# untitled.net
KiCad netlist of a schematic drawn in EAGLE
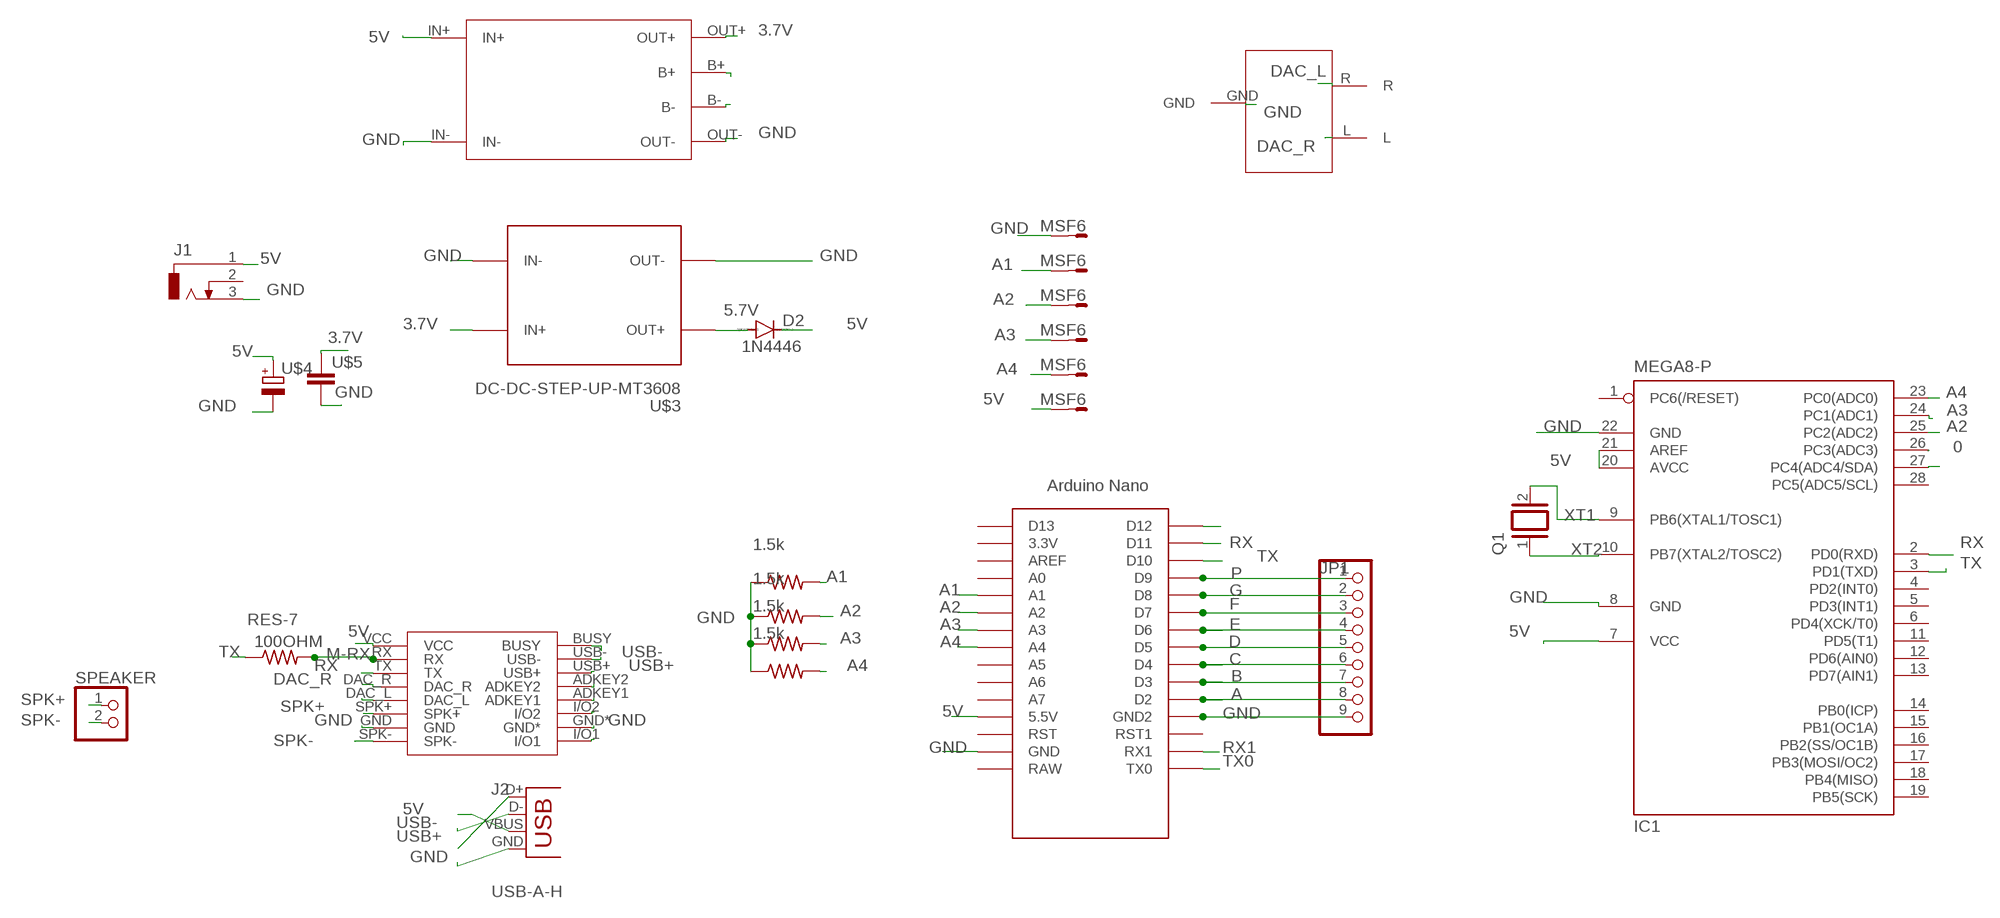
[diagram p0: schematic, sheet 1]

(export (version "E")
  (design (tool "Eeschema 10.0.6"))
  (components
    (comp (ref "1.5K")
      (value "1.5k")
      (footprint "eagle-import:0204_7")
      (libsource (lib "eagle-import") (part "RES-7"))
    )
    (comp (ref "100OHM")
      (value "RES-7")
      (footprint "eagle-import:0204_7")
      (libsource (lib "eagle-import") (part "RES-7"))
    )
    (comp (ref "100OHM2")
      (value "1.5k")
      (footprint "eagle-import:0204_7")
      (libsource (lib "eagle-import") (part "RES-7"))
    )
    (comp (ref "100OHM3")
      (value "1.5k")
      (footprint "eagle-import:0204_7")
      (libsource (lib "eagle-import") (part "RES-7"))
    )
    (comp (ref "100OHM4")
      (value "1.5k")
      (footprint "eagle-import:0204_7")
      (libsource (lib "eagle-import") (part "RES-7"))
    )
    (comp (ref "D2")
      (value "1N4446")
      (footprint "eagle-import:DO35-10")
      (libsource (lib "eagle-import") (part "1N4446"))
    )
    (comp (ref "IC1")
      (value "MEGA8-P")
      (footprint "eagle-import:DIL28-3")
      (libsource (lib "eagle-import") (part "MEGA8-P"))
    )
    (comp (ref "J1")
      (value "CON_JACK")
      (footprint "eagle-import:DCJ0303")
      (libsource (lib "eagle-import") (part "CON_JACK"))
    )
    (comp (ref "J2")
      (value "USB-A-H")
      (footprint "eagle-import:USB-A-H")
      (libsource (lib "eagle-import") (part "USB-A-H"))
    )
    (comp (ref "JP1")
      (value "PINHD-1X9")
      (footprint "eagle-import:1X09")
      (libsource (lib "eagle-import") (part "PINHD-1X9"))
    )
    (comp (ref "Q1")
      (value "XTAL/S")
      (footprint "eagle-import:QS")
      (libsource (lib "eagle-import") (part "XTAL/S"))
    )
    (comp (ref "SPEAKER")
      (value "PINHD-1X2")
      (footprint "eagle-import:1X02")
      (libsource (lib "eagle-import") (part "PINHD-1X2"))
    )
    (comp (ref "ST1")
      (value "MSF6")
      (footprint "eagle-import:MSF6")
      (libsource (lib "eagle-import") (part "MSF6"))
    )
    (comp (ref "U$1")
      (value "ARDUINO_NANO")
      (footprint "eagle-import:NANO")
      (libsource (lib "eagle-import") (part "ARDUINO_NANO"))
    )
    (comp (ref "U$2")
      (value "MP3_MODULE")
      (footprint "eagle-import:MP3_MODULE")
      (libsource (lib "eagle-import") (part "MP3_MODULE"))
    )
    (comp (ref "U$3")
      (value "DC-DC-STEP-UP-MT3608")
      (footprint "eagle-import:DC-DC-STEP-UP-MT3608")
      (libsource (lib "eagle-import") (part "DC-DC-STEP-UP-MT3608"))
    )
    (comp (ref "U$4")
      (value "CAP_POL")
      (footprint "eagle-import:E3,5-8")
      (libsource (lib "eagle-import") (part "CAP_POL"))
    )
    (comp (ref "U$5")
      (value "CAPACITOR")
      (footprint "eagle-import:C025-025X050")
      (libsource (lib "eagle-import") (part "CAPACITOR"))
    )
    (comp (ref "U$6")
      (value "LITHIUM_CHARGER_2A")
      (footprint "eagle-import:LITHIUM-CHARGER-1A")
      (libsource (lib "eagle-import") (part "LITHIUM_CHARGER_2A"))
    )
    (comp (ref "U$7")
      (value "EAR-PHONE-SOCKET")
      (footprint "eagle-import:EAR-PHONE-SOCKET")
      (libsource (lib "eagle-import") (part "EAR-PHONE-SOCKET"))
    )
  )
  (nets
    (net (code "1") (name "/0") (class "Default")
      (node (ref "IC1") (pin "26") (pinfunction "PC3(ADC3)_26") (pintype "bidirectional"))
    )
    (net (code "2") (name "/3.7V") (class "Default")
      (node (ref "U$3") (pin "IN+") (pinfunction "IN+_IN+") (pintype "bidirectional"))
      (node (ref "U$5") (pin "1") (pinfunction "1_1") (pintype "passive"))
      (node (ref "U$6") (pin "OUT+") (pinfunction "OUT+_OUT+") (pintype "bidirectional"))
    )
    (net (code "3") (name "/5.7V") (class "Default")
      (node (ref "D2") (pin "A") (pinfunction "A_A") (pintype "passive"))
      (node (ref "U$3") (pin "OUT+") (pinfunction "OUT+_OUT+") (pintype "bidirectional"))
    )
    (net (code "4") (name "/5V") (class "Default")
      (node (ref "D2") (pin "C") (pinfunction "C_C") (pintype "passive"))
      (node (ref "IC1") (pin "20") (pinfunction "AVCC_20") (pintype "power_in"))
      (node (ref "IC1") (pin "21") (pinfunction "AREF_21") (pintype "passive"))
      (node (ref "IC1") (pin "7") (pinfunction "VCC_7") (pintype "power_in"))
      (node (ref "J1") (pin "1") (pinfunction "1_1") (pintype "passive"))
      (node (ref "J2") (pin "VBUS") (pinfunction "VBUS_VBUS") (pintype "bidirectional"))
      (node (ref "ST1") (pin "1") (pinfunction "S_1") (pintype "passive"))
      (node (ref "U$1") (pin "5V") (pinfunction "5.5V_5V") (pintype "bidirectional"))
      (node (ref "U$2") (pin "VCC") (pinfunction "VCC_VCC") (pintype "bidirectional"))
      (node (ref "U$4") (pin "+") (pinfunction "+_+") (pintype "passive"))
      (node (ref "U$6") (pin "IN+") (pinfunction "IN+_IN+") (pintype "bidirectional"))
    )
    (net (code "5") (name "/A") (class "Default")
      (node (ref "JP1") (pin "8") (pinfunction "8_8") (pintype "passive"))
      (node (ref "U$1") (pin "D2") (pinfunction "D2_D2") (pintype "bidirectional"))
    )
    (net (code "6") (name "/A1") (class "Default")
      (node (ref "1.5K") (pin "2") (pinfunction "2_2") (pintype "passive"))
      (node (ref "ST1") (pin "5") (pinfunction "S_5") (pintype "passive"))
      (node (ref "U$1") (pin "A1") (pinfunction "A1_A1") (pintype "bidirectional"))
    )
    (net (code "7") (name "/A2") (class "Default")
      (node (ref "100OHM2") (pin "2") (pinfunction "2_2") (pintype "passive"))
      (node (ref "IC1") (pin "25") (pinfunction "PC2(ADC2)_25") (pintype "bidirectional"))
      (node (ref "ST1") (pin "4") (pinfunction "S_4") (pintype "passive"))
      (node (ref "U$1") (pin "A2") (pinfunction "A2_A2") (pintype "bidirectional"))
    )
    (net (code "8") (name "/A3") (class "Default")
      (node (ref "100OHM3") (pin "2") (pinfunction "2_2") (pintype "passive"))
      (node (ref "IC1") (pin "24") (pinfunction "PC1(ADC1)_24") (pintype "bidirectional"))
      (node (ref "ST1") (pin "3") (pinfunction "S_3") (pintype "passive"))
      (node (ref "U$1") (pin "A3") (pinfunction "A3_A3") (pintype "bidirectional"))
    )
    (net (code "9") (name "/A4") (class "Default")
      (node (ref "100OHM4") (pin "2") (pinfunction "2_2") (pintype "passive"))
      (node (ref "IC1") (pin "23") (pinfunction "PC0(ADC0)_23") (pintype "bidirectional"))
      (node (ref "ST1") (pin "2") (pinfunction "S_2") (pintype "passive"))
      (node (ref "U$1") (pin "A4") (pinfunction "A4_A4") (pintype "bidirectional"))
    )
    (net (code "10") (name "/B") (class "Default")
      (node (ref "JP1") (pin "7") (pinfunction "7_7") (pintype "passive"))
      (node (ref "U$1") (pin "D3") (pinfunction "D3_D3") (pintype "bidirectional"))
    )
    (net (code "11") (name "/C") (class "Default")
      (node (ref "JP1") (pin "6") (pinfunction "6_6") (pintype "passive"))
      (node (ref "U$1") (pin "D4") (pinfunction "D4_D4") (pintype "bidirectional"))
    )
    (net (code "12") (name "/D") (class "Default")
      (node (ref "JP1") (pin "5") (pinfunction "5_5") (pintype "passive"))
      (node (ref "U$1") (pin "D5") (pinfunction "D5_D5") (pintype "bidirectional"))
    )
    (net (code "13") (name "/DAC_L") (class "Default")
      (node (ref "U$2") (pin "DAC_L") (pinfunction "DAC_L_DAC_L") (pintype "bidirectional"))
      (node (ref "U$7") (pin "R") (pinfunction "R_R") (pintype "bidirectional"))
    )
    (net (code "14") (name "/DAC_R") (class "Default")
      (node (ref "U$2") (pin "DAC_R") (pinfunction "DAC_R_DAC_R") (pintype "bidirectional"))
      (node (ref "U$7") (pin "L") (pinfunction "L_L") (pintype "bidirectional"))
    )
    (net (code "15") (name "/E") (class "Default")
      (node (ref "JP1") (pin "4") (pinfunction "4_4") (pintype "passive"))
      (node (ref "U$1") (pin "D6") (pinfunction "D6_D6") (pintype "bidirectional"))
    )
    (net (code "16") (name "/F") (class "Default")
      (node (ref "JP1") (pin "3") (pinfunction "3_3") (pintype "passive"))
      (node (ref "U$1") (pin "D7") (pinfunction "D7_D7") (pintype "bidirectional"))
    )
    (net (code "17") (name "/G") (class "Default")
      (node (ref "JP1") (pin "2") (pinfunction "2_2") (pintype "passive"))
      (node (ref "U$1") (pin "D8") (pinfunction "D8_D8") (pintype "bidirectional"))
    )
    (net (code "18") (name "/GND") (class "Default")
      (node (ref "1.5K") (pin "1") (pinfunction "1_1") (pintype "passive"))
      (node (ref "100OHM2") (pin "1") (pinfunction "1_1") (pintype "passive"))
      (node (ref "100OHM3") (pin "1") (pinfunction "1_1") (pintype "passive"))
      (node (ref "100OHM4") (pin "1") (pinfunction "1_1") (pintype "passive"))
      (node (ref "IC1") (pin "22") (pinfunction "GND_22") (pintype "power_in"))
      (node (ref "IC1") (pin "8") (pinfunction "GND_8") (pintype "power_in"))
      (node (ref "J1") (pin "3") (pinfunction "3_3") (pintype "passive"))
      (node (ref "J2") (pin "GND") (pinfunction "GND_GND") (pintype "bidirectional"))
      (node (ref "JP1") (pin "9") (pinfunction "9_9") (pintype "passive"))
      (node (ref "ST1") (pin "6") (pinfunction "S_6") (pintype "passive"))
      (node (ref "U$1") (pin "GND") (pinfunction "GND_GND") (pintype "bidirectional"))
      (node (ref "U$1") (pin "GND1") (pinfunction "GND2_GND1") (pintype "bidirectional"))
      (node (ref "U$2") (pin "GND") (pinfunction "GND_GND") (pintype "bidirectional"))
      (node (ref "U$2") (pin "GND*") (pinfunction "GND*_GND*") (pintype "bidirectional"))
      (node (ref "U$3") (pin "IN-") (pinfunction "IN-_IN-") (pintype "bidirectional"))
      (node (ref "U$3") (pin "OUT-") (pinfunction "OUT-_OUT-") (pintype "bidirectional"))
      (node (ref "U$4") (pin "-") (pinfunction "-_-") (pintype "passive"))
      (node (ref "U$5") (pin "2") (pinfunction "2_2") (pintype "passive"))
      (node (ref "U$6") (pin "IN-") (pinfunction "IN-_IN-") (pintype "bidirectional"))
      (node (ref "U$6") (pin "OUT-") (pinfunction "OUT-_OUT-") (pintype "bidirectional"))
      (node (ref "U$7") (pin "GND") (pinfunction "GND_GND") (pintype "bidirectional"))
    )
    (net (code "19") (name "/M-RX") (class "Default")
      (node (ref "100OHM") (pin "2") (pinfunction "2_2") (pintype "passive"))
      (node (ref "U$2") (pin "RX") (pinfunction "RX_RX") (pintype "bidirectional"))
    )
    (net (code "20") (name "/P") (class "Default")
      (node (ref "JP1") (pin "1") (pinfunction "1_1") (pintype "passive"))
      (node (ref "U$1") (pin "D9") (pinfunction "D9_D9") (pintype "bidirectional"))
    )
    (net (code "21") (name "/RX") (class "Default")
      (node (ref "IC1") (pin "2") (pinfunction "PD0(RXD)_2") (pintype "bidirectional"))
      (node (ref "U$1") (pin "D11") (pinfunction "D11_D11") (pintype "bidirectional"))
      (node (ref "U$2") (pin "TX") (pinfunction "TX_TX") (pintype "bidirectional"))
    )
    (net (code "22") (name "/RX1") (class "Default")
      (node (ref "U$1") (pin "RX1") (pinfunction "RX1_RX1") (pintype "bidirectional"))
    )
    (net (code "23") (name "/SPK+") (class "Default")
      (node (ref "SPEAKER") (pin "1") (pinfunction "1_1") (pintype "passive"))
      (node (ref "U$2") (pin "SPK+") (pinfunction "SPK+_SPK+") (pintype "bidirectional"))
    )
    (net (code "24") (name "/SPK-") (class "Default")
      (node (ref "SPEAKER") (pin "2") (pinfunction "2_2") (pintype "passive"))
      (node (ref "U$2") (pin "SPK-") (pinfunction "SPK-_SPK-") (pintype "bidirectional"))
    )
    (net (code "25") (name "/TX") (class "Default")
      (node (ref "100OHM") (pin "1") (pinfunction "1_1") (pintype "passive"))
      (node (ref "IC1") (pin "3") (pinfunction "PD1(TXD)_3") (pintype "bidirectional"))
      (node (ref "U$1") (pin "D10") (pinfunction "D10_D10") (pintype "bidirectional"))
    )
    (net (code "26") (name "/TX0") (class "Default")
      (node (ref "U$1") (pin "TX0") (pinfunction "TX0_TX0") (pintype "bidirectional"))
    )
    (net (code "27") (name "/USB+") (class "Default")
      (node (ref "J2") (pin "D+") (pinfunction "D+_D+") (pintype "bidirectional"))
      (node (ref "U$2") (pin "USB+") (pinfunction "USB+_USB+") (pintype "bidirectional"))
    )
    (net (code "28") (name "/USB-") (class "Default")
      (node (ref "J2") (pin "D-") (pinfunction "D-_D-") (pintype "bidirectional"))
      (node (ref "U$2") (pin "USB-") (pinfunction "USB-_USB-") (pintype "bidirectional"))
    )
    (net (code "29") (name "/XT1") (class "Default")
      (node (ref "IC1") (pin "9") (pinfunction "PB6(XTAL1/TOSC1)_9") (pintype "bidirectional"))
      (node (ref "Q1") (pin "2") (pinfunction "2_2") (pintype "passive"))
    )
    (net (code "30") (name "/XT2") (class "Default")
      (node (ref "IC1") (pin "10") (pinfunction "PB7(XTAL2/TOSC2)_10") (pintype "bidirectional"))
      (node (ref "Q1") (pin "1") (pinfunction "1_1") (pintype "passive"))
    )
    (net (code "31") (name "unconnected-(IC1-PB0(ICP)-Pad14)") (class "Default")
      (node (ref "IC1") (pin "14") (pinfunction "PB0(ICP)_14") (pintype "bidirectional"))
    )
    (net (code "32") (name "unconnected-(IC1-PB1(OC1A)-Pad15)") (class "Default")
      (node (ref "IC1") (pin "15") (pinfunction "PB1(OC1A)_15") (pintype "bidirectional"))
    )
    (net (code "33") (name "unconnected-(IC1-PB2(SS{slash}OC1B)-Pad16)") (class "Default")
      (node (ref "IC1") (pin "16") (pinfunction "PB2(SS/OC1B)_16") (pintype "bidirectional"))
    )
    (net (code "34") (name "unconnected-(IC1-PB3(MOSI{slash}OC2)-Pad17)") (class "Default")
      (node (ref "IC1") (pin "17") (pinfunction "PB3(MOSI/OC2)_17") (pintype "bidirectional"))
    )
    (net (code "35") (name "unconnected-(IC1-PB4(MISO)-Pad18)") (class "Default")
      (node (ref "IC1") (pin "18") (pinfunction "PB4(MISO)_18") (pintype "bidirectional"))
    )
    (net (code "36") (name "unconnected-(IC1-PB5(SCK)-Pad19)") (class "Default")
      (node (ref "IC1") (pin "19") (pinfunction "PB5(SCK)_19") (pintype "bidirectional"))
    )
    (net (code "37") (name "unconnected-(IC1-PC4(ADC4{slash}SDA)-Pad27)") (class "Default")
      (node (ref "IC1") (pin "27") (pinfunction "PC4(ADC4/SDA)_27") (pintype "bidirectional"))
    )
    (net (code "38") (name "unconnected-(IC1-PC5(ADC5{slash}SCL)-Pad28)") (class "Default")
      (node (ref "IC1") (pin "28") (pinfunction "PC5(ADC5/SCL)_28") (pintype "bidirectional"))
    )
    (net (code "39") (name "unconnected-(IC1-PC6({slash}RESET)-Pad1)") (class "Default")
      (node (ref "IC1") (pin "1") (pinfunction "PC6(/RESET)_1") (pintype "bidirectional"))
    )
    (net (code "40") (name "unconnected-(IC1-PD2(INT0)-Pad4)") (class "Default")
      (node (ref "IC1") (pin "4") (pinfunction "PD2(INT0)_4") (pintype "bidirectional"))
    )
    (net (code "41") (name "unconnected-(IC1-PD3(INT1)-Pad5)") (class "Default")
      (node (ref "IC1") (pin "5") (pinfunction "PD3(INT1)_5") (pintype "bidirectional"))
    )
    (net (code "42") (name "unconnected-(IC1-PD4(XCK{slash}T0)-Pad6)") (class "Default")
      (node (ref "IC1") (pin "6") (pinfunction "PD4(XCK/T0)_6") (pintype "bidirectional"))
    )
    (net (code "43") (name "unconnected-(IC1-PD5(T1)-Pad11)") (class "Default")
      (node (ref "IC1") (pin "11") (pinfunction "PD5(T1)_11") (pintype "bidirectional"))
    )
    (net (code "44") (name "unconnected-(IC1-PD6(AIN0)-Pad12)") (class "Default")
      (node (ref "IC1") (pin "12") (pinfunction "PD6(AIN0)_12") (pintype "bidirectional"))
    )
    (net (code "45") (name "unconnected-(IC1-PD7(AIN1)-Pad13)") (class "Default")
      (node (ref "IC1") (pin "13") (pinfunction "PD7(AIN1)_13") (pintype "bidirectional"))
    )
    (net (code "46") (name "unconnected-(J1-Pad2)") (class "Default")
      (node (ref "J1") (pin "2") (pinfunction "2_2") (pintype "passive"))
    )
    (net (code "47") (name "unconnected-(U$1-Pad3.3V)") (class "Default")
      (node (ref "U$1") (pin "3.3V") (pinfunction "3.3V_3.3V") (pintype "bidirectional"))
    )
    (net (code "48") (name "unconnected-(U$1-PadA0)") (class "Default")
      (node (ref "U$1") (pin "A0") (pinfunction "A0_A0") (pintype "bidirectional"))
    )
    (net (code "49") (name "unconnected-(U$1-PadA5)") (class "Default")
      (node (ref "U$1") (pin "A5") (pinfunction "A5_A5") (pintype "bidirectional"))
    )
    (net (code "50") (name "unconnected-(U$1-PadA6)") (class "Default")
      (node (ref "U$1") (pin "A6") (pinfunction "A6_A6") (pintype "bidirectional"))
    )
    (net (code "51") (name "unconnected-(U$1-PadA7)") (class "Default")
      (node (ref "U$1") (pin "A7") (pinfunction "A7_A7") (pintype "bidirectional"))
    )
    (net (code "52") (name "unconnected-(U$1-PadAREF)") (class "Default")
      (node (ref "U$1") (pin "AREF") (pinfunction "AREF_AREF") (pintype "bidirectional"))
    )
    (net (code "53") (name "unconnected-(U$1-PadD12)") (class "Default")
      (node (ref "U$1") (pin "D12") (pinfunction "D12_D12") (pintype "bidirectional"))
    )
    (net (code "54") (name "unconnected-(U$1-PadD13)") (class "Default")
      (node (ref "U$1") (pin "D13") (pinfunction "D13_D13") (pintype "bidirectional"))
    )
    (net (code "55") (name "unconnected-(U$1-PadRAW)") (class "Default")
      (node (ref "U$1") (pin "RAW") (pinfunction "RAW_RAW") (pintype "bidirectional"))
    )
    (net (code "56") (name "unconnected-(U$1-PadRST)") (class "Default")
      (node (ref "U$1") (pin "RST") (pinfunction "RST_RST") (pintype "bidirectional"))
    )
    (net (code "57") (name "unconnected-(U$1-PadRST1)") (class "Default")
      (node (ref "U$1") (pin "RST1") (pinfunction "RST1_RST1") (pintype "bidirectional"))
    )
    (net (code "58") (name "unconnected-(U$2-PadADKEY1)") (class "Default")
      (node (ref "U$2") (pin "ADKEY1") (pinfunction "ADKEY1_ADKEY1") (pintype "bidirectional"))
    )
    (net (code "59") (name "unconnected-(U$2-PadADKEY2)") (class "Default")
      (node (ref "U$2") (pin "ADKEY2") (pinfunction "ADKEY2_ADKEY2") (pintype "bidirectional"))
    )
    (net (code "60") (name "unconnected-(U$2-PadBUSY)") (class "Default")
      (node (ref "U$2") (pin "BUSY") (pinfunction "BUSY_BUSY") (pintype "bidirectional"))
    )
    (net (code "61") (name "unconnected-(U$2-PadI{slash}O1)") (class "Default")
      (node (ref "U$2") (pin "I/O1") (pinfunction "I/O1_I/O1") (pintype "bidirectional"))
    )
    (net (code "62") (name "unconnected-(U$2-PadI{slash}O2)") (class "Default")
      (node (ref "U$2") (pin "I/O2") (pinfunction "I/O2_I/O2") (pintype "bidirectional"))
    )
    (net (code "63") (name "unconnected-(U$6-PadB+)") (class "Default")
      (node (ref "U$6") (pin "B+") (pinfunction "B+_B+") (pintype "bidirectional"))
    )
    (net (code "64") (name "unconnected-(U$6-PadB-)") (class "Default")
      (node (ref "U$6") (pin "B-") (pinfunction "B-_B-") (pintype "bidirectional"))
    )
  )
)
